# CPU.net
KiCad netlist of a schematic drawn in Altium Designer
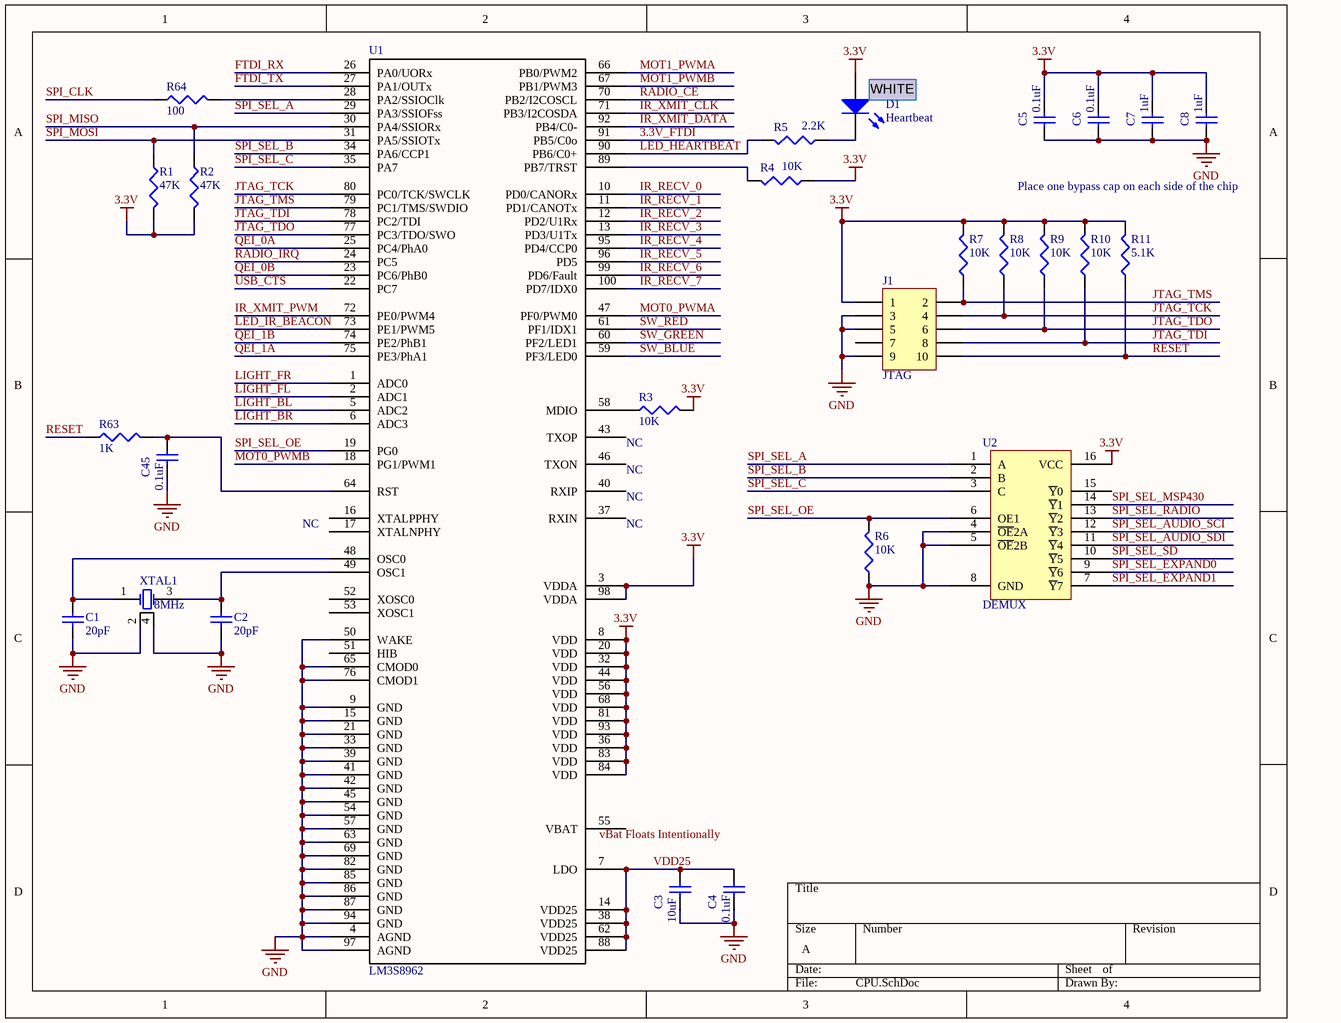
[diagram p0: CPU.SchDoc]

(export (version "E")
  (design (tool "Eeschema 10.0.6"))
  (components
    (comp (ref "C1")
      (value "20pF")
      (footprint "CAPC1005L")
      (description "Capacitor (Semiconductor SIM Model)")
      (fields
        (field (name "PART NUMBER") "GRM15551H200JZ01D")
        (field (name "MANUFACTURER") "Murata")
        (field (name "PUBLISHER") "Altium Limited")
      )
      (libsource (lib "Miscellaneous Devices") (part "Cap Semi"))
    )
    (comp (ref "C2")
      (value "20pF")
      (footprint "CAPC1005L")
      (description "Capacitor (Semiconductor SIM Model)")
      (fields
        (field (name "PART NUMBER") "GRM15551H200JZ01D")
        (field (name "MANUFACTURER") "Murata")
        (field (name "PUBLISHER") "Altium Limited")
      )
      (libsource (lib "Miscellaneous Devices") (part "Cap Semi"))
    )
    (comp (ref "C3")
      (value "10uF")
      (footprint "CAPC1608L")
      (description "Capacitor (Semiconductor SIM Model)")
      (fields
        (field (name "PART NUMBER") "GRM188R60J106ME47J")
        (field (name "MANUFACTURER") "Murata")
        (field (name "PUBLISHER") "Altium Limited")
      )
      (libsource (lib "Miscellaneous Devices") (part "Cap Semi"))
    )
    (comp (ref "C4")
      (value "0.1uF")
      (footprint "CAPC1005L")
      (description "Capacitor (Semiconductor SIM Model)")
      (fields
        (field (name "PART NUMBER") "C1005X5R1A104M050BA")
        (field (name "MANUFACTURER") "TDK")
        (field (name "PUBLISHER") "Altium Limited")
      )
      (libsource (lib "Miscellaneous Devices") (part "Cap Semi"))
    )
    (comp (ref "C5")
      (value "0.1uF")
      (footprint "CAPC1005L")
      (description "Capacitor (Semiconductor SIM Model)")
      (fields
        (field (name "PART NUMBER") "C1005X5R1A104M050BA")
        (field (name "MANUFACTURER") "TDK")
        (field (name "PUBLISHER") "Altium Limited")
      )
      (libsource (lib "Miscellaneous Devices") (part "Cap Semi"))
    )
    (comp (ref "C6")
      (value "0.1uF")
      (footprint "CAPC1005L")
      (description "Capacitor (Semiconductor SIM Model)")
      (fields
        (field (name "PART NUMBER") "C1005X5R1A104M050BA")
        (field (name "MANUFACTURER") "TDK")
        (field (name "PUBLISHER") "Altium Limited")
      )
      (libsource (lib "Miscellaneous Devices") (part "Cap Semi"))
    )
    (comp (ref "C7")
      (value "1uF")
      (footprint "CAPC1608L")
      (description "Capacitor (Semiconductor SIM Model)")
      (fields
        (field (name "PART NUMBER") "C1608Y5V1C105Z")
        (field (name "MANUFACTURER") "TDK")
        (field (name "PUBLISHER") "Altium Limited")
      )
      (libsource (lib "Miscellaneous Devices") (part "Cap Semi"))
    )
    (comp (ref "C8")
      (value "1uF")
      (footprint "CAPC1608L")
      (description "Capacitor (Semiconductor SIM Model)")
      (fields
        (field (name "PART NUMBER") "C1608Y5V1C105Z")
        (field (name "MANUFACTURER") "TDK")
        (field (name "PUBLISHER") "Altium Limited")
      )
      (libsource (lib "Miscellaneous Devices") (part "Cap Semi"))
    )
    (comp (ref "C45")
      (value "0.1uF")
      (footprint "CAPC1005L")
      (description "Capacitor (Semiconductor SIM Model)")
      (fields
        (field (name "PART NUMBER") "C1005X5R1A104M050BA")
        (field (name "MANUFACTURER") "TDK")
        (field (name "PUBLISHER") "Altium Limited")
      )
      (libsource (lib "Miscellaneous Devices") (part "Cap Semi"))
    )
    (comp (ref "D1")
      (value "Heartbeat")
      (footprint "SurfaceMount(603)")
      (fields (field (name "PART NUMBER") "LTW-C193TS5") (field (name "MANUFACTURER") "Lite-ON"))
      (libsource (lib "mrone") (part "LED"))
    )
    (comp (ref "J1")
      (value "JTAG")
      (footprint "JTAG-10")
      (description "Header, 5-Pin, Dual row, Right Angle")
      (fields
        (field (name "PART NUMBER") "SHF-105-01-L-D-SM")
        (field (name "MANUFACTURER") "Samtec")
        (field (name "PUBLISHER") "Altium Limited")
      )
      (libsource (lib "Miscellaneous Connectors") (part "Header 5X2H"))
    )
    (comp (ref "R1")
      (value "47K")
      (footprint "RESC1608L")
      (description "Resistor")
      (fields
        (field (name "PART NUMBER") "ERJ-3GEYJ473V")
        (field (name "MANUFACTURER") "Panasonic")
        (field (name "PUBLISHER") "Altium Limited")
      )
      (libsource (lib "Miscellaneous Devices") (part "Res3"))
    )
    (comp (ref "R2")
      (value "47K")
      (footprint "RESC1608L")
      (description "Resistor")
      (fields
        (field (name "PART NUMBER") "ERJ-3GEYJ473V")
        (field (name "MANUFACTURER") "Panasonic")
        (field (name "PUBLISHER") "Altium Limited")
      )
      (libsource (lib "Miscellaneous Devices") (part "Res3"))
    )
    (comp (ref "R3")
      (value "10K")
      (footprint "RESC1608L")
      (description "Resistor")
      (fields
        (field (name "PART NUMBER") "SR03-1002")
        (field (name "MANUFACTURER") "Vishay")
        (field (name "PUBLISHER") "Altium Limited")
      )
      (libsource (lib "Miscellaneous Devices") (part "Res3"))
    )
    (comp (ref "R4")
      (value "10K")
      (footprint "RESC1608L")
      (description "Resistor")
      (fields
        (field (name "PART NUMBER") "SR03-1002")
        (field (name "MANUFACTURER") "Vishay")
        (field (name "PUBLISHER") "Altium Limited")
      )
      (libsource (lib "Miscellaneous Devices") (part "Res3"))
    )
    (comp (ref "R5")
      (value "2.2K")
      (footprint "RESC1608L")
      (description "Resistor")
      (fields
        (field (name "PART NUMBER") "ERJ-3GEYJ-222V")
        (field (name "MANUFACTURER") "Panasonic")
        (field (name "PUBLISHER") "Altium Limited")
      )
      (libsource (lib "Miscellaneous Devices") (part "Res3"))
    )
    (comp (ref "R6")
      (value "10K")
      (footprint "RESC1608L")
      (description "Resistor")
      (fields
        (field (name "PART NUMBER") "SR03-1002")
        (field (name "MANUFACTURER") "Vishay")
        (field (name "PUBLISHER") "Altium Limited")
      )
      (libsource (lib "Miscellaneous Devices") (part "Res3"))
    )
    (comp (ref "R7")
      (value "10K")
      (footprint "RESC1608L")
      (description "Resistor")
      (fields
        (field (name "PART NUMBER") "SR03-1002")
        (field (name "MANUFACTURER") "Vishay")
        (field (name "PUBLISHER") "Altium Limited")
      )
      (libsource (lib "Miscellaneous Devices") (part "Res3"))
    )
    (comp (ref "R8")
      (value "10K")
      (footprint "RESC1608L")
      (description "Resistor")
      (fields
        (field (name "PART NUMBER") "SR03-1002")
        (field (name "MANUFACTURER") "Vishay")
        (field (name "PUBLISHER") "Altium Limited")
      )
      (libsource (lib "Miscellaneous Devices") (part "Res3"))
    )
    (comp (ref "R9")
      (value "10K")
      (footprint "RESC1608L")
      (description "Resistor")
      (fields
        (field (name "PART NUMBER") "SR03-1002")
        (field (name "MANUFACTURER") "Vishay")
        (field (name "PUBLISHER") "Altium Limited")
      )
      (libsource (lib "Miscellaneous Devices") (part "Res3"))
    )
    (comp (ref "R10")
      (value "10K")
      (footprint "RESC1608L")
      (description "Resistor")
      (fields
        (field (name "PART NUMBER") "SR03-1002")
        (field (name "MANUFACTURER") "Vishay")
        (field (name "PUBLISHER") "Altium Limited")
      )
      (libsource (lib "Miscellaneous Devices") (part "Res3"))
    )
    (comp (ref "R11")
      (value "5.1K")
      (footprint "RESC1608L")
      (description "Resistor")
      (fields
        (field (name "PART NUMBER") "RC0603FR-075K1L")
        (field (name "MANUFACTURER") "Yageo")
        (field (name "PUBLISHER") "Altium Limited")
      )
      (libsource (lib "Miscellaneous Devices") (part "Res3"))
    )
    (comp (ref "R63")
      (value "1K")
      (footprint "RESC1608L")
      (description "Resistor")
      (fields
        (field (name "PART NUMBER") "SR03-1001")
        (field (name "MANUFACTURER") "Vishay")
        (field (name "PUBLISHER") "Altium Limited")
      )
      (libsource (lib "Miscellaneous Devices") (part "Res3"))
    )
    (comp (ref "R64")
      (value "100")
      (footprint "RESC1608L")
      (description "Resistor")
      (fields
        (field (name "PART NUMBER") "ERJ-3GEYJ101V")
        (field (name "MANUFACTURER") "Panasonic")
        (field (name "PUBLISHER") "Altium Limited")
      )
      (libsource (lib "Miscellaneous Devices") (part "Res3"))
    )
    (comp (ref "U1")
      (value "LM3S8962")
      (footprint "LQFP-100")
      (fields (field (name "MANUFACTURER") "TI"))
      (libsource (lib "Schematic Components") (part "LM3S8962"))
    )
    (comp (ref "U2")
      (value "DEMUX")
      (footprint "TSSOP-16")
      (fields (field (name "PART NUMBER") "SN74HC138PWR") (field (name "MANUFACTURER") "TI"))
      (libsource (lib "mrone") (part "DEMUX"))
    )
    (comp (ref "XTAL1")
      (value "8MHz")
      (footprint "CRYSTAL")
      (fields (field (name "PART NUMBER") "ABM3B-8.000MHZ-10-1-U-T") (field (name "MANUFACTURER") "Abracon"))
      (libsource (lib "mrone") (part "Crystal"))
    )
  )
  (nets
    (net (code "1") (name "/3.3V_FTDI") (class "Default")
      (node (ref "U1") (pin "91") (pinfunction "PB5/C0o_91") (pintype "passive"))
    )
    (net (code "2") (name "/FTDI_RX") (class "Default")
      (node (ref "U1") (pin "26") (pinfunction "PA0/UORx_26") (pintype "passive"))
    )
    (net (code "3") (name "/FTDI_TX") (class "Default")
      (node (ref "U1") (pin "27") (pinfunction "PA1/OUTx_27") (pintype "passive"))
    )
    (net (code "4") (name "/IR_RECV_0") (class "Default")
      (node (ref "U1") (pin "10") (pinfunction "PD0/CANORx_10") (pintype "passive"))
    )
    (net (code "5") (name "/IR_RECV_1") (class "Default")
      (node (ref "U1") (pin "11") (pinfunction "PD1/CANOTx_11") (pintype "passive"))
    )
    (net (code "6") (name "/IR_RECV_2") (class "Default")
      (node (ref "U1") (pin "12") (pinfunction "PD2/U1Rx_12") (pintype "passive"))
    )
    (net (code "7") (name "/IR_RECV_3") (class "Default")
      (node (ref "U1") (pin "13") (pinfunction "PD3/U1Tx_13") (pintype "passive"))
    )
    (net (code "8") (name "/IR_RECV_4") (class "Default")
      (node (ref "U1") (pin "95") (pinfunction "PD4/CCP0_95") (pintype "passive"))
    )
    (net (code "9") (name "/IR_RECV_5") (class "Default")
      (node (ref "U1") (pin "96") (pinfunction "PD5_96") (pintype "passive"))
    )
    (net (code "10") (name "/IR_RECV_6") (class "Default")
      (node (ref "U1") (pin "99") (pinfunction "PD6/Fault_99") (pintype "passive"))
    )
    (net (code "11") (name "/IR_RECV_7") (class "Default")
      (node (ref "U1") (pin "100") (pinfunction "PD7/IDX0_100") (pintype "passive"))
    )
    (net (code "12") (name "/IR_XMIT_CLK") (class "Default")
      (node (ref "U1") (pin "71") (pinfunction "PB3/I2COSDA_71") (pintype "passive"))
    )
    (net (code "13") (name "/IR_XMIT_DATA") (class "Default")
      (node (ref "U1") (pin "92") (pinfunction "PB4/C0-_92") (pintype "passive"))
    )
    (net (code "14") (name "/IR_XMIT_PWM") (class "Default")
      (node (ref "U1") (pin "72") (pinfunction "PE0/PWM4_72") (pintype "passive"))
    )
    (net (code "15") (name "/JTAG_TCK") (class "Default")
      (node (ref "J1") (pin "4") (pinfunction "4_4") (pintype "passive"))
      (node (ref "R8") (pin "1") (pinfunction "1_1") (pintype "passive"))
      (node (ref "U1") (pin "80") (pinfunction "PC0/TCK/SWCLK_80") (pintype "passive"))
    )
    (net (code "16") (name "/JTAG_TDI") (class "Default")
      (node (ref "J1") (pin "8") (pinfunction "8_8") (pintype "passive"))
      (node (ref "R10") (pin "1") (pinfunction "1_1") (pintype "passive"))
      (node (ref "U1") (pin "78") (pinfunction "PC2/TDI_78") (pintype "passive"))
    )
    (net (code "17") (name "/JTAG_TDO") (class "Default")
      (node (ref "J1") (pin "6") (pinfunction "6_6") (pintype "passive"))
      (node (ref "R9") (pin "1") (pinfunction "1_1") (pintype "passive"))
      (node (ref "U1") (pin "77") (pinfunction "PC3/TDO/SWO_77") (pintype "passive"))
    )
    (net (code "18") (name "/JTAG_TMS") (class "Default")
      (node (ref "J1") (pin "2") (pinfunction "2_2") (pintype "passive"))
      (node (ref "R7") (pin "1") (pinfunction "1_1") (pintype "passive"))
      (node (ref "U1") (pin "79") (pinfunction "PC1/TMS/SWDIO_79") (pintype "passive"))
    )
    (net (code "19") (name "/LED_HEARTBEAT") (class "Default")
      (node (ref "R5") (pin "2") (pinfunction "2_2") (pintype "passive"))
      (node (ref "U1") (pin "90") (pinfunction "PB6/C0+_90") (pintype "passive"))
    )
    (net (code "20") (name "/LED_IR_BEACON") (class "Default")
      (node (ref "U1") (pin "73") (pinfunction "PE1/PWM5_73") (pintype "passive"))
    )
    (net (code "21") (name "/LIGHT_BL") (class "Default")
      (node (ref "U1") (pin "5") (pinfunction "ADC2_5") (pintype "passive"))
    )
    (net (code "22") (name "/LIGHT_BR") (class "Default")
      (node (ref "U1") (pin "6") (pinfunction "ADC3_6") (pintype "passive"))
    )
    (net (code "23") (name "/LIGHT_FL") (class "Default")
      (node (ref "U1") (pin "2") (pinfunction "ADC1_2") (pintype "passive"))
    )
    (net (code "24") (name "/LIGHT_FR") (class "Default")
      (node (ref "U1") (pin "1") (pinfunction "ADC0_1") (pintype "passive"))
    )
    (net (code "25") (name "/MOT0_PWMA") (class "Default")
      (node (ref "U1") (pin "47") (pinfunction "PF0/PWM0_47") (pintype "passive"))
    )
    (net (code "26") (name "/MOT0_PWMB") (class "Default")
      (node (ref "U1") (pin "18") (pinfunction "PG1/PWM1_18") (pintype "passive"))
    )
    (net (code "27") (name "/MOT1_PWMA") (class "Default")
      (node (ref "U1") (pin "66") (pinfunction "PB0/PWM2_66") (pintype "passive"))
    )
    (net (code "28") (name "/MOT1_PWMB") (class "Default")
      (node (ref "U1") (pin "67") (pinfunction "PB1/PWM3_67") (pintype "passive"))
    )
    (net (code "29") (name "/QEI_0A") (class "Default")
      (node (ref "U1") (pin "25") (pinfunction "PC4/PhA0_25") (pintype "passive"))
    )
    (net (code "30") (name "/QEI_0B") (class "Default")
      (node (ref "U1") (pin "23") (pinfunction "PC6/PhB0_23") (pintype "passive"))
    )
    (net (code "31") (name "/QEI_1A") (class "Default")
      (node (ref "U1") (pin "75") (pinfunction "PE3/PhA1_75") (pintype "passive"))
    )
    (net (code "32") (name "/QEI_1B") (class "Default")
      (node (ref "U1") (pin "74") (pinfunction "PE2/PhB1_74") (pintype "passive"))
    )
    (net (code "33") (name "/RADIO_CE") (class "Default")
      (node (ref "U1") (pin "70") (pinfunction "PB2/I2COSCL_70") (pintype "passive"))
    )
    (net (code "34") (name "/RADIO_IRQ") (class "Default")
      (node (ref "U1") (pin "24") (pinfunction "PC5_24") (pintype "passive"))
    )
    (net (code "35") (name "/RESET") (class "Default")
      (node (ref "J1") (pin "10") (pinfunction "10_10") (pintype "passive"))
      (node (ref "R11") (pin "1") (pinfunction "1_1") (pintype "passive"))
      (node (ref "R63") (pin "1") (pinfunction "1_1") (pintype "passive"))
    )
    (net (code "36") (name "/SPI_CLK") (class "Default")
      (node (ref "R64") (pin "1") (pinfunction "1_1") (pintype "passive"))
    )
    (net (code "37") (name "/SPI_MISO") (class "Default")
      (node (ref "R2") (pin "1") (pinfunction "1_1") (pintype "passive"))
      (node (ref "U1") (pin "30") (pinfunction "PA4/SSIORx_30") (pintype "passive"))
    )
    (net (code "38") (name "/SPI_MOSI") (class "Default")
      (node (ref "R1") (pin "1") (pinfunction "1_1") (pintype "passive"))
      (node (ref "U1") (pin "31") (pinfunction "PA5/SSIOTx_31") (pintype "passive"))
    )
    (net (code "39") (name "/SPI_SEL_A") (class "Default")
      (node (ref "U1") (pin "29") (pinfunction "PA3/SSIOFss_29") (pintype "passive"))
      (node (ref "U2") (pin "1") (pinfunction "A_1") (pintype "passive"))
    )
    (net (code "40") (name "/SPI_SEL_AUDIO_SCI") (class "Default")
      (node (ref "U2") (pin "12") (pinfunction "~{Y}3_12") (pintype "passive"))
    )
    (net (code "41") (name "/SPI_SEL_AUDIO_SDI") (class "Default")
      (node (ref "U2") (pin "11") (pinfunction "~{Y}4_11") (pintype "passive"))
    )
    (net (code "42") (name "/SPI_SEL_B") (class "Default")
      (node (ref "U1") (pin "34") (pinfunction "PA6/CCP1_34") (pintype "passive"))
      (node (ref "U2") (pin "2") (pinfunction "B_2") (pintype "passive"))
    )
    (net (code "43") (name "/SPI_SEL_C") (class "Default")
      (node (ref "U1") (pin "35") (pinfunction "PA7_35") (pintype "passive"))
      (node (ref "U2") (pin "3") (pinfunction "C_3") (pintype "passive"))
    )
    (net (code "44") (name "/SPI_SEL_EXPAND0") (class "Default")
      (node (ref "U2") (pin "9") (pinfunction "~{Y}6_9") (pintype "passive"))
    )
    (net (code "45") (name "/SPI_SEL_EXPAND1") (class "Default")
      (node (ref "U2") (pin "7") (pinfunction "~{Y}7_7") (pintype "passive"))
    )
    (net (code "46") (name "/SPI_SEL_MSP430") (class "Default")
      (node (ref "U2") (pin "14") (pinfunction "~{Y}1_14") (pintype "passive"))
    )
    (net (code "47") (name "/SPI_SEL_OE") (class "Default")
      (node (ref "R6") (pin "2") (pinfunction "2_2") (pintype "passive"))
      (node (ref "U1") (pin "19") (pinfunction "PG0_19") (pintype "passive"))
      (node (ref "U2") (pin "6") (pinfunction "OE1_6") (pintype "passive"))
    )
    (net (code "48") (name "/SPI_SEL_RADIO") (class "Default")
      (node (ref "U2") (pin "13") (pinfunction "~{Y}2_13") (pintype "passive"))
    )
    (net (code "49") (name "/SPI_SEL_SD") (class "Default")
      (node (ref "U2") (pin "10") (pinfunction "~{Y}5_10") (pintype "passive"))
    )
    (net (code "50") (name "/SW_BLUE") (class "Default")
      (node (ref "U1") (pin "59") (pinfunction "PF3/LED0_59") (pintype "passive"))
    )
    (net (code "51") (name "/SW_GREEN") (class "Default")
      (node (ref "U1") (pin "60") (pinfunction "PF2/LED1_60") (pintype "passive"))
    )
    (net (code "52") (name "/SW_RED") (class "Default")
      (node (ref "U1") (pin "61") (pinfunction "PF1/IDX1_61") (pintype "passive"))
    )
    (net (code "53") (name "/USB_CTS") (class "Default")
      (node (ref "U1") (pin "22") (pinfunction "PC7_22") (pintype "passive"))
    )
    (net (code "54") (name "/VDD25") (class "Default")
      (node (ref "C3") (pin "2") (pinfunction "2_2") (pintype "passive"))
      (node (ref "C4") (pin "2") (pinfunction "2_2") (pintype "passive"))
      (node (ref "U1") (pin "14") (pinfunction "VDD25_14") (pintype "passive"))
      (node (ref "U1") (pin "38") (pinfunction "VDD25_38") (pintype "passive"))
      (node (ref "U1") (pin "62") (pinfunction "VDD25_62") (pintype "passive"))
      (node (ref "U1") (pin "7") (pinfunction "LDO_7") (pintype "passive"))
      (node (ref "U1") (pin "88") (pinfunction "VDD25_88") (pintype "passive"))
    )
    (net (code "55") (name "3.3V") (class "Default")
      (node (ref "C5") (pin "2") (pinfunction "2_2") (pintype "passive"))
      (node (ref "C6") (pin "2") (pinfunction "2_2") (pintype "passive"))
      (node (ref "C7") (pin "2") (pinfunction "2_2") (pintype "passive"))
      (node (ref "C8") (pin "2") (pinfunction "2_2") (pintype "passive"))
      (node (ref "D1") (pin "1") (pinfunction "A_1") (pintype "passive"))
      (node (ref "J1") (pin "1") (pinfunction "1_1") (pintype "passive"))
      (node (ref "R1") (pin "2") (pinfunction "2_2") (pintype "passive"))
      (node (ref "R10") (pin "2") (pinfunction "2_2") (pintype "passive"))
      (node (ref "R11") (pin "2") (pinfunction "2_2") (pintype "passive"))
      (node (ref "R2") (pin "2") (pinfunction "2_2") (pintype "passive"))
      (node (ref "R3") (pin "2") (pinfunction "2_2") (pintype "passive"))
      (node (ref "R4") (pin "1") (pinfunction "1_1") (pintype "passive"))
      (node (ref "R7") (pin "2") (pinfunction "2_2") (pintype "passive"))
      (node (ref "R8") (pin "2") (pinfunction "2_2") (pintype "passive"))
      (node (ref "R9") (pin "2") (pinfunction "2_2") (pintype "passive"))
      (node (ref "U1") (pin "20") (pinfunction "VDD_20") (pintype "passive"))
      (node (ref "U1") (pin "3") (pinfunction "VDDA_3") (pintype "passive"))
      (node (ref "U1") (pin "32") (pinfunction "VDD_32") (pintype "passive"))
      (node (ref "U1") (pin "36") (pinfunction "VDD_36") (pintype "passive"))
      (node (ref "U1") (pin "44") (pinfunction "VDD_44") (pintype "passive"))
      (node (ref "U1") (pin "56") (pinfunction "VDD_56") (pintype "passive"))
      (node (ref "U1") (pin "68") (pinfunction "VDD_68") (pintype "passive"))
      (node (ref "U1") (pin "8") (pinfunction "VDD_8") (pintype "passive"))
      (node (ref "U1") (pin "81") (pinfunction "VDD_81") (pintype "passive"))
      (node (ref "U1") (pin "83") (pinfunction "VDD_83") (pintype "passive"))
      (node (ref "U1") (pin "84") (pinfunction "VDD_84") (pintype "passive"))
      (node (ref "U1") (pin "93") (pinfunction "VDD_93") (pintype "passive"))
      (node (ref "U1") (pin "98") (pinfunction "VDDA_98") (pintype "passive"))
      (node (ref "U2") (pin "16") (pinfunction "VCC_16") (pintype "passive"))
    )
    (net (code "56") (name "GND") (class "Default")
      (node (ref "C1") (pin "1") (pinfunction "1_1") (pintype "passive"))
      (node (ref "C2") (pin "1") (pinfunction "1_1") (pintype "passive"))
      (node (ref "C3") (pin "1") (pinfunction "1_1") (pintype "passive"))
      (node (ref "C4") (pin "1") (pinfunction "1_1") (pintype "passive"))
      (node (ref "C45") (pin "1") (pinfunction "1_1") (pintype "passive"))
      (node (ref "C5") (pin "1") (pinfunction "1_1") (pintype "passive"))
      (node (ref "C6") (pin "1") (pinfunction "1_1") (pintype "passive"))
      (node (ref "C7") (pin "1") (pinfunction "1_1") (pintype "passive"))
      (node (ref "C8") (pin "1") (pinfunction "1_1") (pintype "passive"))
      (node (ref "J1") (pin "3") (pinfunction "3_3") (pintype "passive"))
      (node (ref "J1") (pin "5") (pinfunction "5_5") (pintype "passive"))
      (node (ref "J1") (pin "9") (pinfunction "9_9") (pintype "passive"))
      (node (ref "R6") (pin "1") (pinfunction "1_1") (pintype "passive"))
      (node (ref "U1") (pin "15") (pinfunction "GND_15") (pintype "passive"))
      (node (ref "U1") (pin "21") (pinfunction "GND_21") (pintype "passive"))
      (node (ref "U1") (pin "33") (pinfunction "GND_33") (pintype "passive"))
      (node (ref "U1") (pin "39") (pinfunction "GND_39") (pintype "passive"))
      (node (ref "U1") (pin "4") (pinfunction "AGND_4") (pintype "passive"))
      (node (ref "U1") (pin "41") (pinfunction "GND_41") (pintype "passive"))
      (node (ref "U1") (pin "42") (pinfunction "GND_42") (pintype "passive"))
      (node (ref "U1") (pin "45") (pinfunction "GND_45") (pintype "passive"))
      (node (ref "U1") (pin "50") (pinfunction "WAKE_50") (pintype "passive"))
      (node (ref "U1") (pin "54") (pinfunction "GND_54") (pintype "passive"))
      (node (ref "U1") (pin "57") (pinfunction "GND_57") (pintype "passive"))
      (node (ref "U1") (pin "63") (pinfunction "GND_63") (pintype "passive"))
      (node (ref "U1") (pin "65") (pinfunction "CMOD0_65") (pintype "passive"))
      (node (ref "U1") (pin "69") (pinfunction "GND_69") (pintype "passive"))
      (node (ref "U1") (pin "76") (pinfunction "CMOD1_76") (pintype "passive"))
      (node (ref "U1") (pin "82") (pinfunction "GND_82") (pintype "passive"))
      (node (ref "U1") (pin "85") (pinfunction "GND_85") (pintype "passive"))
      (node (ref "U1") (pin "86") (pinfunction "GND_86") (pintype "passive"))
      (node (ref "U1") (pin "87") (pinfunction "GND_87") (pintype "passive"))
      (node (ref "U1") (pin "9") (pinfunction "GND_9") (pintype "passive"))
      (node (ref "U1") (pin "94") (pinfunction "GND_94") (pintype "passive"))
      (node (ref "U1") (pin "97") (pinfunction "AGND_97") (pintype "passive"))
      (node (ref "U2") (pin "4") (pinfunction "~{OE}2A_4") (pintype "passive"))
      (node (ref "U2") (pin "5") (pinfunction "~{OE}2B_5") (pintype "passive"))
      (node (ref "U2") (pin "8") (pinfunction "GND_8") (pintype "passive"))
      (node (ref "XTAL1") (pin "2") (pinfunction "GND_2") (pintype "passive"))
      (node (ref "XTAL1") (pin "4") (pinfunction "GND_4") (pintype "passive"))
    )
    (net (code "57") (name "Net-(D1-K)") (class "Default")
      (node (ref "D1") (pin "2") (pinfunction "K_2") (pintype "passive"))
      (node (ref "R5") (pin "1") (pinfunction "1_1") (pintype "passive"))
    )
    (net (code "58") (name "Net-(U1-MDIO)") (class "Default")
      (node (ref "R3") (pin "1") (pinfunction "1_1") (pintype "passive"))
      (node (ref "U1") (pin "58") (pinfunction "MDIO_58") (pintype "passive"))
    )
    (net (code "59") (name "Net-(U1-OSC0)") (class "Default")
      (node (ref "C1") (pin "2") (pinfunction "2_2") (pintype "passive"))
      (node (ref "U1") (pin "48") (pinfunction "OSC0_48") (pintype "passive"))
      (node (ref "XTAL1") (pin "1") (pinfunction "OSC1_1") (pintype "passive"))
    )
    (net (code "60") (name "Net-(U1-OSC1)") (class "Default")
      (node (ref "C2") (pin "2") (pinfunction "2_2") (pintype "passive"))
      (node (ref "U1") (pin "49") (pinfunction "OSC1_49") (pintype "passive"))
      (node (ref "XTAL1") (pin "3") (pinfunction "OSC2_3") (pintype "passive"))
    )
    (net (code "61") (name "Net-(U1-PA2{slash}SSIOClk)") (class "Default")
      (node (ref "R64") (pin "2") (pinfunction "2_2") (pintype "passive"))
      (node (ref "U1") (pin "28") (pinfunction "PA2/SSIOClk_28") (pintype "passive"))
    )
    (net (code "62") (name "Net-(U1-PB7{slash}TRST)") (class "Default")
      (node (ref "R4") (pin "2") (pinfunction "2_2") (pintype "passive"))
      (node (ref "U1") (pin "89") (pinfunction "PB7/TRST_89") (pintype "passive"))
    )
    (net (code "63") (name "Net-(U1-RST)") (class "Default")
      (node (ref "C45") (pin "2") (pinfunction "2_2") (pintype "passive"))
      (node (ref "R63") (pin "2") (pinfunction "2_2") (pintype "passive"))
      (node (ref "U1") (pin "64") (pinfunction "RST_64") (pintype "passive"))
    )
    (net (code "64") (name "unconnected-(J1-Pad7)") (class "Default")
      (node (ref "J1") (pin "7") (pinfunction "7_7") (pintype "passive"))
    )
    (net (code "65") (name "unconnected-(U1-HIB-Pad51)") (class "Default")
      (node (ref "U1") (pin "51") (pinfunction "HIB_51") (pintype "passive"))
    )
    (net (code "66") (name "unconnected-(U1-RXIN-Pad37)") (class "Default")
      (node (ref "U1") (pin "37") (pinfunction "RXIN_37") (pintype "passive"))
    )
    (net (code "67") (name "unconnected-(U1-RXIP-Pad40)") (class "Default")
      (node (ref "U1") (pin "40") (pinfunction "RXIP_40") (pintype "passive"))
    )
    (net (code "68") (name "unconnected-(U1-TXON-Pad46)") (class "Default")
      (node (ref "U1") (pin "46") (pinfunction "TXON_46") (pintype "passive"))
    )
    (net (code "69") (name "unconnected-(U1-TXOP-Pad43)") (class "Default")
      (node (ref "U1") (pin "43") (pinfunction "TXOP_43") (pintype "passive"))
    )
    (net (code "70") (name "unconnected-(U1-VBAT-Pad55)") (class "Default")
      (node (ref "U1") (pin "55") (pinfunction "VBAT_55") (pintype "passive"))
    )
    (net (code "71") (name "unconnected-(U1-XOSC0-Pad52)") (class "Default")
      (node (ref "U1") (pin "52") (pinfunction "XOSC0_52") (pintype "passive"))
    )
    (net (code "72") (name "unconnected-(U1-XOSC1-Pad53)") (class "Default")
      (node (ref "U1") (pin "53") (pinfunction "XOSC1_53") (pintype "passive"))
    )
    (net (code "73") (name "unconnected-(U1-XTALNPHY-Pad17)") (class "Default")
      (node (ref "U1") (pin "17") (pinfunction "XTALNPHY_17") (pintype "passive"))
    )
    (net (code "74") (name "unconnected-(U1-XTALPPHY-Pad16)") (class "Default")
      (node (ref "U1") (pin "16") (pinfunction "XTALPPHY_16") (pintype "passive"))
    )
    (net (code "75") (name "unconnected-(U2-~{Y}0-Pad15)") (class "Default")
      (node (ref "U2") (pin "15") (pinfunction "~{Y}0_15") (pintype "passive"))
    )
  )
)
